# Neopixel_Class.net
KiCad netlist of a schematic drawn in Altium Designer
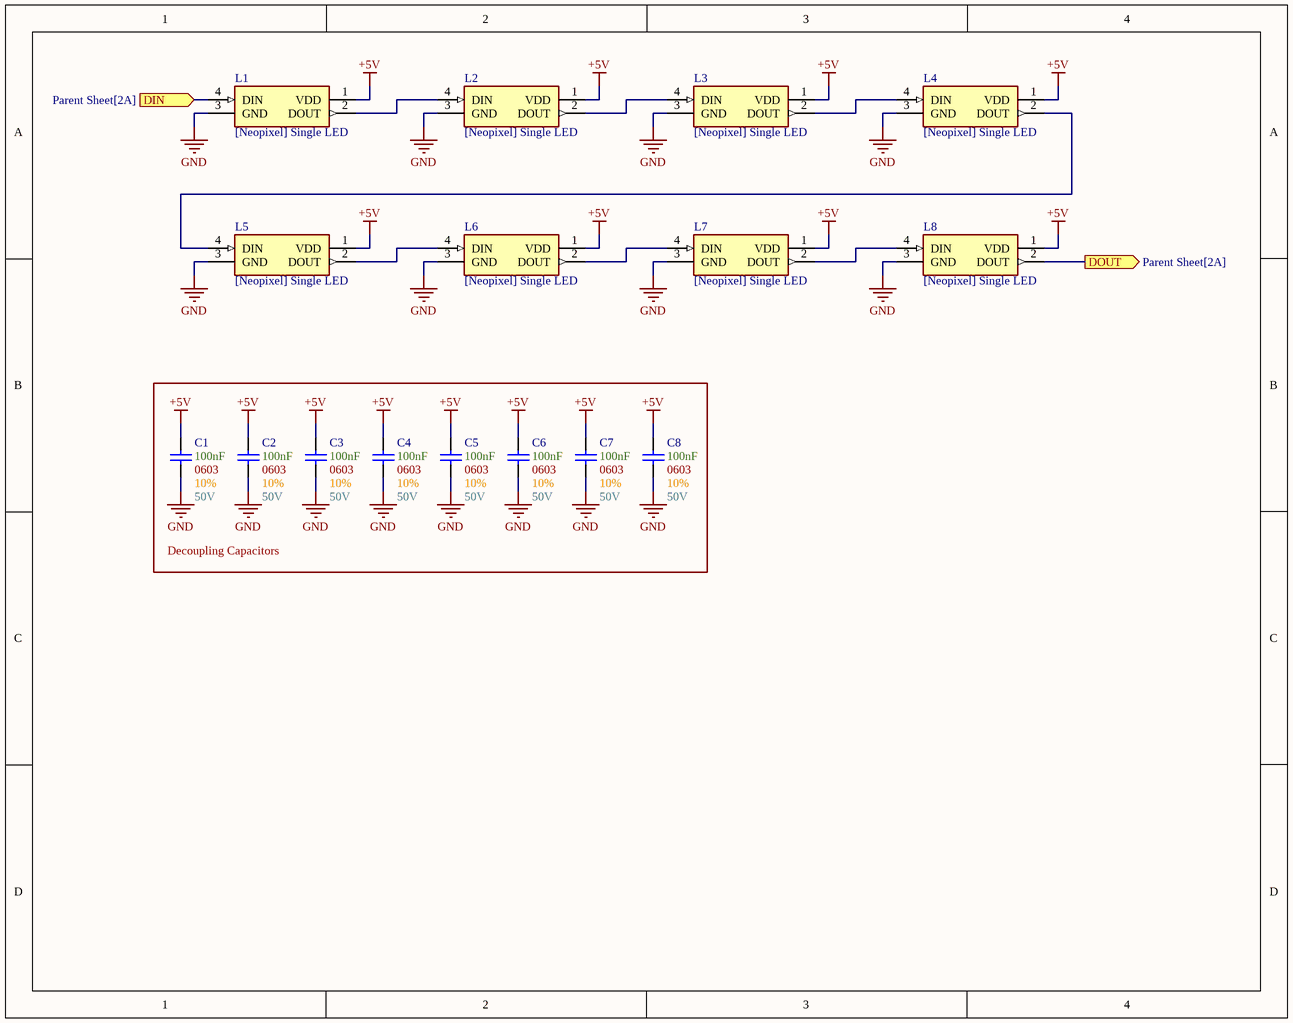
[diagram p0: Neopixel Class.SchDoc]

(export (version "E")
  (design (tool "Eeschema 10.0.6"))
  (components
    (comp (ref "C1")
      (value "[Cap] 0603 0.1uF 10% 50V")
      (footprint "[Cap] SMD 0603")
      (description "CL10B104KB8NNNC")
      (fields
        (field (name "MAX VOLTAGE") "50V")
        (field (name "SIZE PACKAGE") "0603")
        (field (name "TOLERANCE") "10%")
        (field (name "CAPACITANCE") "100nF")
      )
      (libsource (lib "Capacitors") (part "[Cap] 0603 0.1uF 10% 50V"))
    )
    (comp (ref "C2")
      (value "[Cap] 0603 0.1uF 10% 50V")
      (footprint "[Cap] SMD 0603")
      (description "CL10B104KB8NNNC")
      (fields
        (field (name "MAX VOLTAGE") "50V")
        (field (name "SIZE PACKAGE") "0603")
        (field (name "TOLERANCE") "10%")
        (field (name "CAPACITANCE") "100nF")
      )
      (libsource (lib "Capacitors") (part "[Cap] 0603 0.1uF 10% 50V"))
    )
    (comp (ref "C3")
      (value "[Cap] 0603 0.1uF 10% 50V")
      (footprint "[Cap] SMD 0603")
      (description "CL10B104KB8NNNC")
      (fields
        (field (name "MAX VOLTAGE") "50V")
        (field (name "SIZE PACKAGE") "0603")
        (field (name "TOLERANCE") "10%")
        (field (name "CAPACITANCE") "100nF")
      )
      (libsource (lib "Capacitors") (part "[Cap] 0603 0.1uF 10% 50V"))
    )
    (comp (ref "C4")
      (value "[Cap] 0603 0.1uF 10% 50V")
      (footprint "[Cap] SMD 0603")
      (description "CL10B104KB8NNNC")
      (fields
        (field (name "MAX VOLTAGE") "50V")
        (field (name "SIZE PACKAGE") "0603")
        (field (name "TOLERANCE") "10%")
        (field (name "CAPACITANCE") "100nF")
      )
      (libsource (lib "Capacitors") (part "[Cap] 0603 0.1uF 10% 50V"))
    )
    (comp (ref "C5")
      (value "[Cap] 0603 0.1uF 10% 50V")
      (footprint "[Cap] SMD 0603")
      (description "CL10B104KB8NNNC")
      (fields
        (field (name "MAX VOLTAGE") "50V")
        (field (name "SIZE PACKAGE") "0603")
        (field (name "TOLERANCE") "10%")
        (field (name "CAPACITANCE") "100nF")
      )
      (libsource (lib "Capacitors") (part "[Cap] 0603 0.1uF 10% 50V"))
    )
    (comp (ref "C6")
      (value "[Cap] 0603 0.1uF 10% 50V")
      (footprint "[Cap] SMD 0603")
      (description "CL10B104KB8NNNC")
      (fields
        (field (name "MAX VOLTAGE") "50V")
        (field (name "SIZE PACKAGE") "0603")
        (field (name "TOLERANCE") "10%")
        (field (name "CAPACITANCE") "100nF")
      )
      (libsource (lib "Capacitors") (part "[Cap] 0603 0.1uF 10% 50V"))
    )
    (comp (ref "C7")
      (value "[Cap] 0603 0.1uF 10% 50V")
      (footprint "[Cap] SMD 0603")
      (description "CL10B104KB8NNNC")
      (fields
        (field (name "MAX VOLTAGE") "50V")
        (field (name "SIZE PACKAGE") "0603")
        (field (name "TOLERANCE") "10%")
        (field (name "CAPACITANCE") "100nF")
      )
      (libsource (lib "Capacitors") (part "[Cap] 0603 0.1uF 10% 50V"))
    )
    (comp (ref "C8")
      (value "[Cap] 0603 0.1uF 10% 50V")
      (footprint "[Cap] SMD 0603")
      (description "CL10B104KB8NNNC")
      (fields
        (field (name "MAX VOLTAGE") "50V")
        (field (name "SIZE PACKAGE") "0603")
        (field (name "TOLERANCE") "10%")
        (field (name "CAPACITANCE") "100nF")
      )
      (libsource (lib "Capacitors") (part "[Cap] 0603 0.1uF 10% 50V"))
    )
    (comp (ref "L1")
      (value "[Neopixel] Single LED")
      (footprint "[Neopixel] Single LED")
      (description "WS2812B")
      (libsource (lib "LEDs") (part "[Neopixel] Single LED"))
    )
    (comp (ref "L2")
      (value "[Neopixel] Single LED")
      (footprint "[Neopixel] Single LED")
      (description "WS2812B")
      (libsource (lib "LEDs") (part "[Neopixel] Single LED"))
    )
    (comp (ref "L3")
      (value "[Neopixel] Single LED")
      (footprint "[Neopixel] Single LED")
      (description "WS2812B")
      (libsource (lib "LEDs") (part "[Neopixel] Single LED"))
    )
    (comp (ref "L4")
      (value "[Neopixel] Single LED")
      (footprint "[Neopixel] Single LED")
      (description "WS2812B")
      (libsource (lib "LEDs") (part "[Neopixel] Single LED"))
    )
    (comp (ref "L5")
      (value "[Neopixel] Single LED")
      (footprint "[Neopixel] Single LED")
      (description "WS2812B")
      (libsource (lib "LEDs") (part "[Neopixel] Single LED"))
    )
    (comp (ref "L6")
      (value "[Neopixel] Single LED")
      (footprint "[Neopixel] Single LED")
      (description "WS2812B")
      (libsource (lib "LEDs") (part "[Neopixel] Single LED"))
    )
    (comp (ref "L7")
      (value "[Neopixel] Single LED")
      (footprint "[Neopixel] Single LED")
      (description "WS2812B")
      (libsource (lib "LEDs") (part "[Neopixel] Single LED"))
    )
    (comp (ref "L8")
      (value "[Neopixel] Single LED")
      (footprint "[Neopixel] Single LED")
      (description "WS2812B")
      (libsource (lib "LEDs") (part "[Neopixel] Single LED"))
    )
  )
  (nets
    (net (code "1") (name "+5V") (class "Default")
      (node (ref "C1") (pin "2") (pinfunction "2_2") (pintype "passive"))
      (node (ref "C2") (pin "2") (pinfunction "2_2") (pintype "passive"))
      (node (ref "C3") (pin "2") (pinfunction "2_2") (pintype "passive"))
      (node (ref "C4") (pin "2") (pinfunction "2_2") (pintype "passive"))
      (node (ref "C5") (pin "2") (pinfunction "2_2") (pintype "passive"))
      (node (ref "C6") (pin "2") (pinfunction "2_2") (pintype "passive"))
      (node (ref "C7") (pin "2") (pinfunction "2_2") (pintype "passive"))
      (node (ref "C8") (pin "2") (pinfunction "2_2") (pintype "passive"))
      (node (ref "L1") (pin "1") (pinfunction "VDD_1") (pintype "power_in"))
      (node (ref "L2") (pin "1") (pinfunction "VDD_1") (pintype "power_in"))
      (node (ref "L3") (pin "1") (pinfunction "VDD_1") (pintype "power_in"))
      (node (ref "L4") (pin "1") (pinfunction "VDD_1") (pintype "power_in"))
      (node (ref "L5") (pin "1") (pinfunction "VDD_1") (pintype "power_in"))
      (node (ref "L6") (pin "1") (pinfunction "VDD_1") (pintype "power_in"))
      (node (ref "L7") (pin "1") (pinfunction "VDD_1") (pintype "power_in"))
      (node (ref "L8") (pin "1") (pinfunction "VDD_1") (pintype "power_in"))
    )
    (net (code "2") (name "/DIN") (class "Default")
      (node (ref "L1") (pin "4") (pinfunction "DIN_4") (pintype "input"))
    )
    (net (code "3") (name "/DOUT") (class "Default")
      (node (ref "L8") (pin "2") (pinfunction "DOUT_2") (pintype "output"))
    )
    (net (code "4") (name "GND") (class "Default")
      (node (ref "C1") (pin "1") (pinfunction "1_1") (pintype "passive"))
      (node (ref "C2") (pin "1") (pinfunction "1_1") (pintype "passive"))
      (node (ref "C3") (pin "1") (pinfunction "1_1") (pintype "passive"))
      (node (ref "C4") (pin "1") (pinfunction "1_1") (pintype "passive"))
      (node (ref "C5") (pin "1") (pinfunction "1_1") (pintype "passive"))
      (node (ref "C6") (pin "1") (pinfunction "1_1") (pintype "passive"))
      (node (ref "C7") (pin "1") (pinfunction "1_1") (pintype "passive"))
      (node (ref "C8") (pin "1") (pinfunction "1_1") (pintype "passive"))
      (node (ref "L1") (pin "3") (pinfunction "GND_3") (pintype "power_in"))
      (node (ref "L2") (pin "3") (pinfunction "GND_3") (pintype "power_in"))
      (node (ref "L3") (pin "3") (pinfunction "GND_3") (pintype "power_in"))
      (node (ref "L4") (pin "3") (pinfunction "GND_3") (pintype "power_in"))
      (node (ref "L5") (pin "3") (pinfunction "GND_3") (pintype "power_in"))
      (node (ref "L6") (pin "3") (pinfunction "GND_3") (pintype "power_in"))
      (node (ref "L7") (pin "3") (pinfunction "GND_3") (pintype "power_in"))
      (node (ref "L8") (pin "3") (pinfunction "GND_3") (pintype "power_in"))
    )
    (net (code "5") (name "Net-(L1-DOUT)") (class "Default")
      (node (ref "L1") (pin "2") (pinfunction "DOUT_2") (pintype "output"))
      (node (ref "L2") (pin "4") (pinfunction "DIN_4") (pintype "input"))
    )
    (net (code "6") (name "Net-(L2-DOUT)") (class "Default")
      (node (ref "L2") (pin "2") (pinfunction "DOUT_2") (pintype "output"))
      (node (ref "L3") (pin "4") (pinfunction "DIN_4") (pintype "input"))
    )
    (net (code "7") (name "Net-(L3-DOUT)") (class "Default")
      (node (ref "L3") (pin "2") (pinfunction "DOUT_2") (pintype "output"))
      (node (ref "L4") (pin "4") (pinfunction "DIN_4") (pintype "input"))
    )
    (net (code "8") (name "Net-(L4-DOUT)") (class "Default")
      (node (ref "L4") (pin "2") (pinfunction "DOUT_2") (pintype "output"))
      (node (ref "L5") (pin "4") (pinfunction "DIN_4") (pintype "input"))
    )
    (net (code "9") (name "Net-(L5-DOUT)") (class "Default")
      (node (ref "L5") (pin "2") (pinfunction "DOUT_2") (pintype "output"))
      (node (ref "L6") (pin "4") (pinfunction "DIN_4") (pintype "input"))
    )
    (net (code "10") (name "Net-(L6-DOUT)") (class "Default")
      (node (ref "L6") (pin "2") (pinfunction "DOUT_2") (pintype "output"))
      (node (ref "L7") (pin "4") (pinfunction "DIN_4") (pintype "input"))
    )
    (net (code "11") (name "Net-(L7-DOUT)") (class "Default")
      (node (ref "L7") (pin "2") (pinfunction "DOUT_2") (pintype "output"))
      (node (ref "L8") (pin "4") (pinfunction "DIN_4") (pintype "input"))
    )
  )
)
